# CAN-Interface.net
KiCad netlist of a schematic drawn in Altium Designer
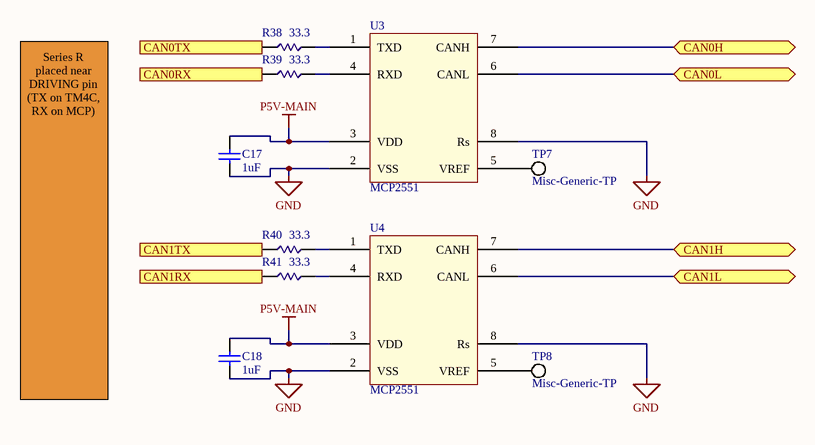
[diagram p0: CAN-Interface.SchDoc]

(export (version "E")
  (design (tool "Eeschema 10.0.6"))
  (components
    (comp (ref "C17")
      (value "1uF")
      (footprint "FOOTPRINT-0805-GEN")
      (description "Capacitor")
      (fields (field (name "Comment") "C0805C105K8RACTU") (field (name "PUBLISHER") "Altium Limited"))
      (libsource (lib "HR-Master-Integrated") (part "Capacitor-Generic-0805"))
    )
    (comp (ref "C18")
      (value "1uF")
      (footprint "FOOTPRINT-0805-GEN")
      (description "Capacitor")
      (fields (field (name "Comment") "C0805C105K8RACTU") (field (name "PUBLISHER") "Altium Limited"))
      (libsource (lib "HR-Master-Integrated") (part "Capacitor-Generic-0805"))
    )
    (comp (ref "R38")
      (value "33.3")
      (footprint "FOOTPRINT-0805-GEN")
      (description "1/8 Watt Surface Mount Resistor")
      (fields (field (name "Comment") "SMC"))
      (libsource (lib "HR-Master-Integrated") (part "Resistor-Generic-0805-2012"))
    )
    (comp (ref "R39")
      (value "33.3")
      (footprint "FOOTPRINT-0805-GEN")
      (description "1/8 Watt Surface Mount Resistor")
      (fields (field (name "Comment") "SMC"))
      (libsource (lib "HR-Master-Integrated") (part "Resistor-Generic-0805-2012"))
    )
    (comp (ref "R40")
      (value "33.3")
      (footprint "FOOTPRINT-0805-GEN")
      (description "1/8 Watt Surface Mount Resistor")
      (fields (field (name "Comment") "SMC"))
      (libsource (lib "HR-Master-Integrated") (part "Resistor-Generic-0805-2012"))
    )
    (comp (ref "R41")
      (value "33.3")
      (footprint "FOOTPRINT-0805-GEN")
      (description "1/8 Watt Surface Mount Resistor")
      (fields (field (name "Comment") "SMC"))
      (libsource (lib "HR-Master-Integrated") (part "Resistor-Generic-0805-2012"))
    )
    (comp (ref "TP7")
      (value "Misc-Generic-TP")
      (footprint "FOOTPRINT-GENERIC-TP-SMD-1MM")
      (libsource (lib "Generic") (part "Misc-Generic-TP"))
    )
    (comp (ref "TP8")
      (value "Misc-Generic-TP")
      (footprint "FOOTPRINT-GENERIC-TP-SMD-1MM")
      (libsource (lib "Generic") (part "Misc-Generic-TP"))
    )
    (comp (ref "U3")
      (value "MCP2551")
      (footprint "FOOTPRINT-SOIC-8PIN")
      (libsource (lib "HR-Master-Integrated") (part "IC-MCP-MCP2551"))
    )
    (comp (ref "U4")
      (value "MCP2551")
      (footprint "FOOTPRINT-SOIC-8PIN")
      (libsource (lib "HR-Master-Integrated") (part "IC-MCP-MCP2551"))
    )
  )
  (nets
    (net (code "1") (name "/CAN0H") (class "Default")
      (node (ref "U3") (pin "7") (pinfunction "CANH_7") (pintype "passive"))
    )
    (net (code "2") (name "/CAN0L") (class "Default")
      (node (ref "U3") (pin "6") (pinfunction "CANL_6") (pintype "passive"))
    )
    (net (code "3") (name "/CAN0RX") (class "Default")
      (node (ref "R39") (pin "1") (pinfunction "1_1") (pintype "passive"))
    )
    (net (code "4") (name "/CAN0TX") (class "Default")
      (node (ref "R38") (pin "1") (pinfunction "1_1") (pintype "passive"))
    )
    (net (code "5") (name "/CAN1H") (class "Default")
      (node (ref "U4") (pin "7") (pinfunction "CANH_7") (pintype "passive"))
    )
    (net (code "6") (name "/CAN1L") (class "Default")
      (node (ref "U4") (pin "6") (pinfunction "CANL_6") (pintype "passive"))
    )
    (net (code "7") (name "/CAN1RX") (class "Default")
      (node (ref "R41") (pin "1") (pinfunction "1_1") (pintype "passive"))
    )
    (net (code "8") (name "/CAN1TX") (class "Default")
      (node (ref "R40") (pin "1") (pinfunction "1_1") (pintype "passive"))
    )
    (net (code "9") (name "GND") (class "Default")
      (node (ref "C17") (pin "1") (pinfunction "1_1") (pintype "passive"))
      (node (ref "C18") (pin "1") (pinfunction "1_1") (pintype "passive"))
      (node (ref "U3") (pin "2") (pinfunction "VSS_2") (pintype "passive"))
      (node (ref "U3") (pin "8") (pinfunction "Rs_8") (pintype "passive"))
      (node (ref "U4") (pin "2") (pinfunction "VSS_2") (pintype "passive"))
      (node (ref "U4") (pin "8") (pinfunction "Rs_8") (pintype "passive"))
    )
    (net (code "10") (name "Net-(TP7-TP)") (class "Default")
      (node (ref "TP7") (pin "1") (pinfunction "TP_1") (pintype "passive"))
      (node (ref "U3") (pin "5") (pinfunction "VREF_5") (pintype "passive"))
    )
    (net (code "11") (name "Net-(TP8-TP)") (class "Default")
      (node (ref "TP8") (pin "1") (pinfunction "TP_1") (pintype "passive"))
      (node (ref "U4") (pin "5") (pinfunction "VREF_5") (pintype "passive"))
    )
    (net (code "12") (name "Net-(U3-RXD)") (class "Default")
      (node (ref "R39") (pin "2") (pinfunction "2_2") (pintype "passive"))
      (node (ref "U3") (pin "4") (pinfunction "RXD_4") (pintype "passive"))
    )
    (net (code "13") (name "Net-(U3-TXD)") (class "Default")
      (node (ref "R38") (pin "2") (pinfunction "2_2") (pintype "passive"))
      (node (ref "U3") (pin "1") (pinfunction "TXD_1") (pintype "passive"))
    )
    (net (code "14") (name "Net-(U4-RXD)") (class "Default")
      (node (ref "R41") (pin "2") (pinfunction "2_2") (pintype "passive"))
      (node (ref "U4") (pin "4") (pinfunction "RXD_4") (pintype "passive"))
    )
    (net (code "15") (name "Net-(U4-TXD)") (class "Default")
      (node (ref "R40") (pin "2") (pinfunction "2_2") (pintype "passive"))
      (node (ref "U4") (pin "1") (pinfunction "TXD_1") (pintype "passive"))
    )
    (net (code "16") (name "P5V-MAIN") (class "Default")
      (node (ref "C17") (pin "2") (pinfunction "2_2") (pintype "passive"))
      (node (ref "C18") (pin "2") (pinfunction "2_2") (pintype "passive"))
      (node (ref "U3") (pin "3") (pinfunction "VDD_3") (pintype "passive"))
      (node (ref "U4") (pin "3") (pinfunction "VDD_3") (pintype "passive"))
    )
  )
)
